# Sensor_node.net
KiCad netlist of a schematic drawn in Altium Designer
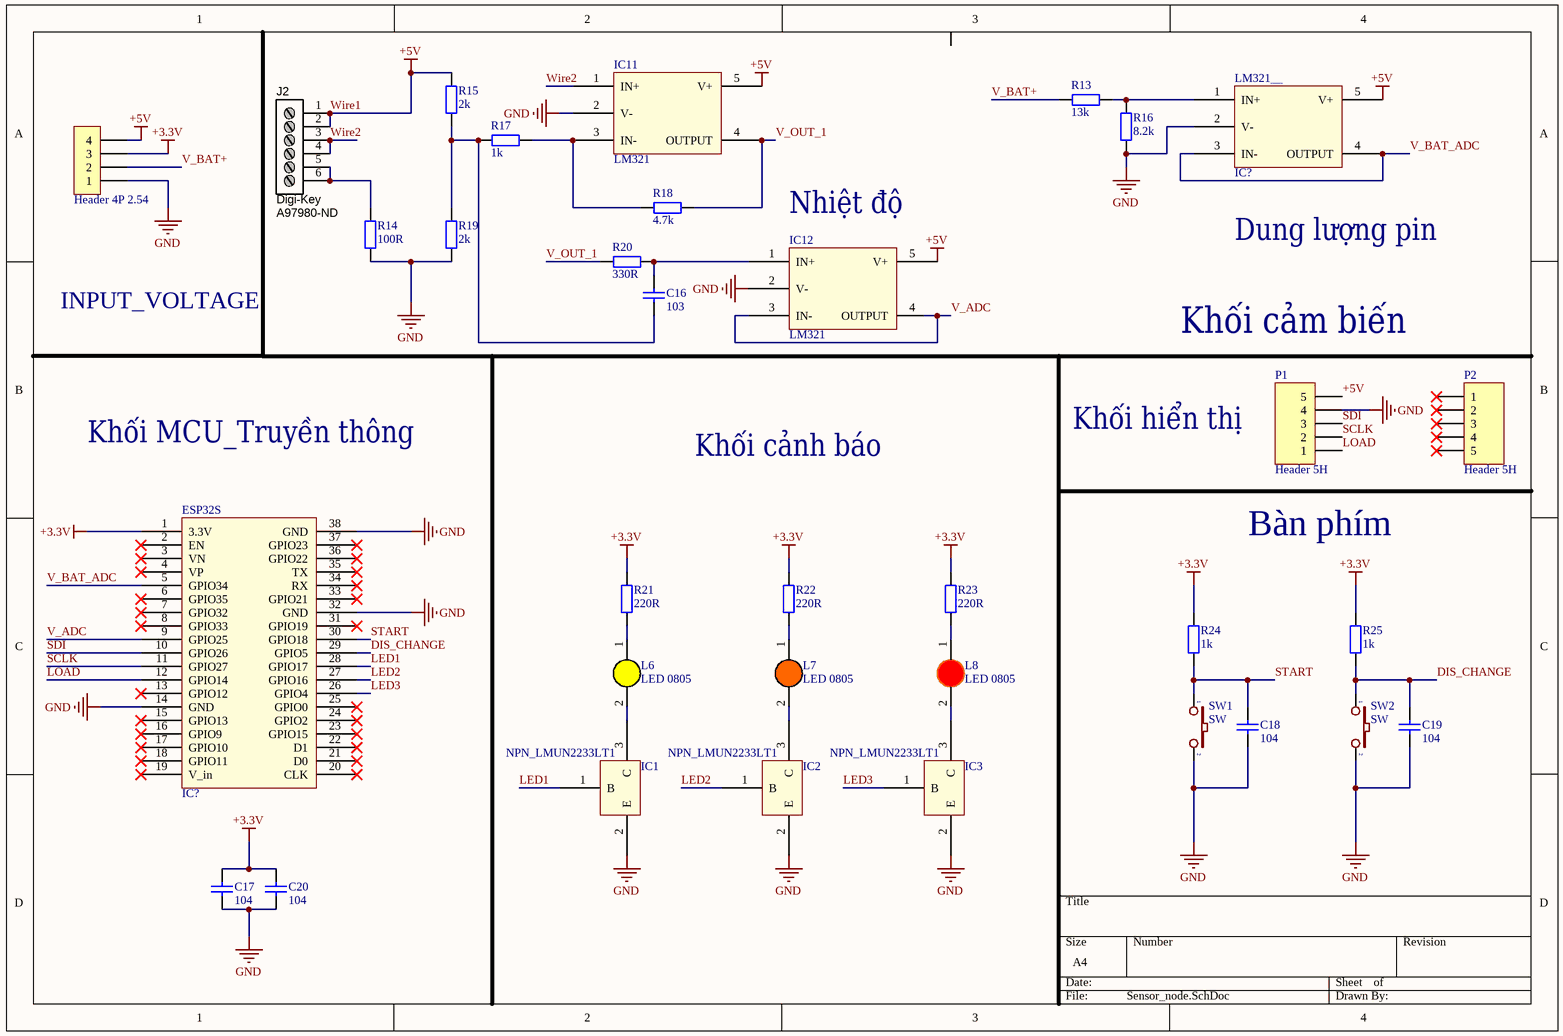
[diagram p0: Sensor_node.SchDoc]

(export (version "E")
  (design (tool "Eeschema 10.0.6"))
  (components
    (comp (ref "C16")
      (value "103")
      (footprint "tu gom")
      (description "Cắm")
      (libsource (lib "Altium_Lib_by_KhueNguyenCreator") (part "Tu gom 103 50V"))
    )
    (comp (ref "C17")
      (value "104")
      (footprint "tu 1206")
      (description "Dán")
      (libsource (lib "Altium_Lib_by_KhueNguyenCreator") (part "Tu 1206 104 50V 20%"))
    )
    (comp (ref "C18")
      (value "104")
      (footprint "tu gom")
      (description "Cắm")
      (libsource (lib "Altium_Lib_by_KhueNguyenCreator") (part "Tu gom 104 50V"))
    )
    (comp (ref "C19")
      (value "104")
      (footprint "tu gom")
      (description "Cắm")
      (libsource (lib "Altium_Lib_by_KhueNguyenCreator") (part "Tu gom 104 50V"))
    )
    (comp (ref "C20")
      (value "104")
      (footprint "tu 1206")
      (description "Dán")
      (libsource (lib "Altium_Lib_by_KhueNguyenCreator") (part "Tu 1206 104 50V 20%"))
    )
    (comp (ref "ESP32S") (value "IC?") (footprint "ESP32 DEVKIT") (libsource (lib "Schlib3") (part "IC?")))
    (comp (ref "H2")
      (value "Header 4P 2.54")
      (footprint "XH2.54M-4")
      (description "Cắm")
      (libsource (lib "Altium_Lib_by_KhueNguyenCreator") (part "Header 4P 2.54 Duc Thang"))
    )
    (comp (ref "IC1")
      (value "NPN_LMUN2233LT1")
      (footprint "SOT23_LMUN2233_trans")
      (libsource (lib "Schlib4") (part "NPN_LMUN2233LT1"))
    )
    (comp (ref "IC2")
      (value "NPN_LMUN2233LT1")
      (footprint "SOT23_LMUN2233_trans")
      (libsource (lib "Schlib4") (part "NPN_LMUN2233LT1"))
    )
    (comp (ref "IC3")
      (value "NPN_LMUN2233LT1")
      (footprint "SOT23_LMUN2233_trans")
      (libsource (lib "Schlib4") (part "NPN_LMUN2233LT1"))
    )
    (comp (ref "IC11") (value "LM321") (footprint "SOT23_LM321") (libsource (lib "Schlib2") (part "LM321")))
    (comp (ref "IC12") (value "LM321") (footprint "SOT23_LM321") (libsource (lib "Schlib2") (part "LM321")))
    (comp (ref "J2")
      (value "Stackable ScrewTerm")
      (footprint "6P_PCB_ScrewTerm_90S_3.81MM")
      (description "Terminal Block, THT, 6-Position screwterm, 3.81mm pitch")
      (fields (field (name "SUPPLIER 1") "Digi-Key") (field (name "SUPPLIER PART NUMBER 1") "A97980-ND"))
      (libsource (lib "My library altium") (part "6P_ScrewTerm_90S_3.81MM"))
    )
    (comp (ref "L6")
      (value "LED 0805")
      (footprint "LED-0805-Yellow")
      (description "Dán")
      (libsource (lib "Altium_Lib_by_KhueNguyenCreator") (part "LED 0805 Vang"))
    )
    (comp (ref "L7")
      (value "LED 0805")
      (footprint "LED-0805-Orange")
      (description "Dán")
      (libsource (lib "Altium_Lib_by_KhueNguyenCreator") (part "LED 0805 Cam"))
    )
    (comp (ref "L8")
      (value "LED 0805")
      (footprint "LED-0805-Red")
      (description "Dán")
      (libsource (lib "Altium_Lib_by_KhueNguyenCreator") (part "LED 0805 Do"))
    )
    (comp (ref "LM321__") (value "IC?") (footprint "SOT23_LM321") (libsource (lib "Schlib2") (part "IC?")))
    (comp (ref "P1")
      (value "Header 5H")
      (footprint "HDR1X5H")
      (description "Header, 5-Pin, Right Angle")
      (fields (field (name "PUBLISHER") "Altium Limited"))
      (libsource (lib "") (part "Header 5H_1"))
    )
    (comp (ref "P2")
      (value "Header 5H")
      (footprint "HDR1X5H")
      (description "Header, 5-Pin, Right Angle")
      (fields (field (name "PUBLISHER") "Altium Limited"))
      (libsource (lib "My library altium") (part "Header 5H"))
    )
    (comp (ref "R13")
      (value "13k")
      (footprint "tro smd 0805")
      (description "Dán")
      (libsource (lib "Altium_Lib_by_KhueNguyenCreator") (part "Tro 0805 5% 12k"))
    )
    (comp (ref "R14")
      (value "100R")
      (footprint "tro smd 1206")
      (description "Dán")
      (libsource (lib "Altium_Lib_by_KhueNguyenCreator") (part "Tro 1206 5% 100R"))
    )
    (comp (ref "R15")
      (value "2k")
      (footprint "tro smd 1206")
      (description "Dán")
      (libsource (lib "Altium_Lib_by_KhueNguyenCreator") (part "Tro 1206 5% 2k"))
    )
    (comp (ref "R16")
      (value "8.2k")
      (footprint "tro smd 0805")
      (description "Dán")
      (libsource (lib "Altium_Lib_by_KhueNguyenCreator") (part "Tro 0805 5% 8.2k"))
    )
    (comp (ref "R17")
      (value "1k")
      (footprint "tro smd 0805")
      (description "Dán")
      (libsource (lib "Altium_Lib_by_KhueNguyenCreator") (part "Tro 0805 5% 1k"))
    )
    (comp (ref "R18")
      (value "4.7k")
      (footprint "tro smd 0805")
      (description "Dán")
      (libsource (lib "Altium_Lib_by_KhueNguyenCreator") (part "Tro 0805 5% 4.7k"))
    )
    (comp (ref "R19")
      (value "2k")
      (footprint "tro smd 1206")
      (description "Dán")
      (libsource (lib "Altium_Lib_by_KhueNguyenCreator") (part "Tro 1206 5% 2k"))
    )
    (comp (ref "R20")
      (value "330R")
      (footprint "Tro SMD 0805")
      (description "Dán")
      (libsource (lib "Altium_Lib_by_KhueNguyenCreator") (part "Tro 0805 5% 330R"))
    )
    (comp (ref "R21")
      (value "220R")
      (footprint "tro smd 0805")
      (description "Dán")
      (libsource (lib "Altium_Lib_by_KhueNguyenCreator") (part "Tro 0805 5% 220R"))
    )
    (comp (ref "R22")
      (value "220R")
      (footprint "tro smd 0805")
      (description "Dán")
      (libsource (lib "Altium_Lib_by_KhueNguyenCreator") (part "Tro 0805 5% 220R"))
    )
    (comp (ref "R23")
      (value "220R")
      (footprint "tro smd 0805")
      (description "Dán")
      (libsource (lib "Altium_Lib_by_KhueNguyenCreator") (part "Tro 0805 5% 220R"))
    )
    (comp (ref "R24")
      (value "1k")
      (footprint "tro smd 0805")
      (description "Dán")
      (libsource (lib "Altium_Lib_by_KhueNguyenCreator") (part "Tro 0805 5% 1k"))
    )
    (comp (ref "R25")
      (value "1k")
      (footprint "tro smd 0805")
      (description "Dán")
      (libsource (lib "Altium_Lib_by_KhueNguyenCreator") (part "Tro 0805 5% 1k"))
    )
    (comp (ref "SW1")
      (value "SW")
      (footprint "SW2")
      (description "Switch button 2 pin")
      (libsource (lib "syhaunguyen") (part "SW2"))
    )
    (comp (ref "SW2")
      (value "SW")
      (footprint "SW2")
      (description "Switch button 2 pin")
      (libsource (lib "syhaunguyen") (part "SW2"))
    )
  )
  (nets
    (net (code "1") (name "+3.3V") (class "Default")
      (node (ref "C17") (pin "1") (pinfunction "1_1") (pintype "passive"))
      (node (ref "C20") (pin "1") (pinfunction "1_1") (pintype "passive"))
      (node (ref "ESP32S") (pin "1") (pinfunction "3.3V_1") (pintype "passive"))
      (node (ref "H2") (pin "3") (pinfunction "3_3") (pintype "passive"))
      (node (ref "R21") (pin "2") (pinfunction "2_2") (pintype "passive"))
      (node (ref "R22") (pin "2") (pinfunction "2_2") (pintype "passive"))
      (node (ref "R23") (pin "2") (pinfunction "2_2") (pintype "passive"))
      (node (ref "R24") (pin "2") (pinfunction "2_2") (pintype "passive"))
      (node (ref "R25") (pin "2") (pinfunction "2_2") (pintype "passive"))
    )
    (net (code "2") (name "+5V") (class "Default")
      (node (ref "H2") (pin "4") (pinfunction "4_4") (pintype "passive"))
      (node (ref "IC11") (pin "5") (pinfunction "V+_5") (pintype "passive"))
      (node (ref "IC12") (pin "5") (pinfunction "V+_5") (pintype "passive"))
      (node (ref "J2") (pin "1") (pinfunction "1_1") (pintype "passive"))
      (node (ref "J2") (pin "2") (pinfunction "2_2") (pintype "passive"))
      (node (ref "LM321__") (pin "5") (pinfunction "V+_5") (pintype "passive"))
      (node (ref "P1") (pin "5") (pinfunction "5_5") (pintype "passive"))
      (node (ref "R15") (pin "2") (pinfunction "2_2") (pintype "passive"))
    )
    (net (code "3") (name "/DIS_CHANGE") (class "Default")
      (node (ref "C19") (pin "1") (pinfunction "1_1") (pintype "passive"))
      (node (ref "ESP32S") (pin "29") (pinfunction "GPIO5_29") (pintype "passive"))
      (node (ref "R25") (pin "1") (pinfunction "1_1") (pintype "passive"))
      (node (ref "SW2") (pin "1") (pinfunction "1_1") (pintype "passive"))
    )
    (net (code "4") (name "/LED1") (class "Default")
      (node (ref "ESP32S") (pin "28") (pinfunction "GPIO17_28") (pintype "passive"))
      (node (ref "IC1") (pin "1") (pinfunction "B_1") (pintype "passive"))
    )
    (net (code "5") (name "/LED2") (class "Default")
      (node (ref "ESP32S") (pin "27") (pinfunction "GPIO16_27") (pintype "passive"))
      (node (ref "IC2") (pin "1") (pinfunction "B_1") (pintype "passive"))
    )
    (net (code "6") (name "/LED3") (class "Default")
      (node (ref "ESP32S") (pin "26") (pinfunction "GPIO4_26") (pintype "passive"))
      (node (ref "IC3") (pin "1") (pinfunction "B_1") (pintype "passive"))
    )
    (net (code "7") (name "/LOAD") (class "Default")
      (node (ref "ESP32S") (pin "12") (pinfunction "GPIO14_12") (pintype "passive"))
      (node (ref "P1") (pin "1") (pinfunction "1_1") (pintype "passive"))
    )
    (net (code "8") (name "/SCLK") (class "Default")
      (node (ref "ESP32S") (pin "11") (pinfunction "GPIO27_11") (pintype "passive"))
      (node (ref "P1") (pin "2") (pinfunction "2_2") (pintype "passive"))
    )
    (net (code "9") (name "/SDI") (class "Default")
      (node (ref "ESP32S") (pin "10") (pinfunction "GPIO26_10") (pintype "passive"))
      (node (ref "P1") (pin "3") (pinfunction "3_3") (pintype "passive"))
    )
    (net (code "10") (name "/START") (class "Default")
      (node (ref "C18") (pin "1") (pinfunction "1_1") (pintype "passive"))
      (node (ref "ESP32S") (pin "30") (pinfunction "GPIO18_30") (pintype "passive"))
      (node (ref "R24") (pin "1") (pinfunction "1_1") (pintype "passive"))
      (node (ref "SW1") (pin "1") (pinfunction "1_1") (pintype "passive"))
    )
    (net (code "11") (name "/V_ADC") (class "Default")
      (node (ref "ESP32S") (pin "9") (pinfunction "GPIO25_9") (pintype "passive"))
      (node (ref "IC12") (pin "3") (pinfunction "IN-_3") (pintype "passive"))
      (node (ref "IC12") (pin "4") (pinfunction "OUTPUT_4") (pintype "passive"))
    )
    (net (code "12") (name "/V_BAT+") (class "Default")
      (node (ref "H2") (pin "2") (pinfunction "2_2") (pintype "passive"))
      (node (ref "R13") (pin "1") (pinfunction "1_1") (pintype "passive"))
    )
    (net (code "13") (name "/V_BAT_ADC") (class "Default")
      (node (ref "ESP32S") (pin "5") (pinfunction "GPIO34_5") (pintype "passive"))
      (node (ref "LM321__") (pin "3") (pinfunction "IN-_3") (pintype "passive"))
      (node (ref "LM321__") (pin "4") (pinfunction "OUTPUT_4") (pintype "passive"))
    )
    (net (code "14") (name "/V_OUT_1") (class "Default")
      (node (ref "IC11") (pin "4") (pinfunction "OUTPUT_4") (pintype "passive"))
      (node (ref "R18") (pin "2") (pinfunction "2_2") (pintype "passive"))
      (node (ref "R20") (pin "1") (pinfunction "1_1") (pintype "passive"))
    )
    (net (code "15") (name "/Wire2") (class "Default")
      (node (ref "IC11") (pin "1") (pinfunction "IN+_1") (pintype "passive"))
      (node (ref "J2") (pin "3") (pinfunction "3_3") (pintype "passive"))
      (node (ref "J2") (pin "4") (pinfunction "4_4") (pintype "passive"))
    )
    (net (code "16") (name "GND") (class "Default")
      (node (ref "C17") (pin "2") (pinfunction "2_2") (pintype "passive"))
      (node (ref "C18") (pin "2") (pinfunction "2_2") (pintype "passive"))
      (node (ref "C19") (pin "2") (pinfunction "2_2") (pintype "passive"))
      (node (ref "C20") (pin "2") (pinfunction "2_2") (pintype "passive"))
      (node (ref "ESP32S") (pin "14") (pinfunction "GND_14") (pintype "passive"))
      (node (ref "ESP32S") (pin "32") (pinfunction "GND_32") (pintype "passive"))
      (node (ref "ESP32S") (pin "38") (pinfunction "GND_38") (pintype "passive"))
      (node (ref "H2") (pin "1") (pinfunction "1_1") (pintype "passive"))
      (node (ref "IC1") (pin "2") (pinfunction "E_2") (pintype "passive"))
      (node (ref "IC11") (pin "2") (pinfunction "V-_2") (pintype "passive"))
      (node (ref "IC12") (pin "2") (pinfunction "V-_2") (pintype "passive"))
      (node (ref "IC2") (pin "2") (pinfunction "E_2") (pintype "passive"))
      (node (ref "IC3") (pin "2") (pinfunction "E_2") (pintype "passive"))
      (node (ref "LM321__") (pin "2") (pinfunction "V-_2") (pintype "passive"))
      (node (ref "P1") (pin "4") (pinfunction "4_4") (pintype "passive"))
      (node (ref "R14") (pin "1") (pinfunction "1_1") (pintype "passive"))
      (node (ref "R16") (pin "1") (pinfunction "1_1") (pintype "passive"))
      (node (ref "R19") (pin "1") (pinfunction "1_1") (pintype "passive"))
      (node (ref "SW1") (pin "2") (pinfunction "2_2") (pintype "passive"))
      (node (ref "SW2") (pin "2") (pinfunction "2_2") (pintype "passive"))
    )
    (net (code "17") (name "Net-(C16-Pad2)") (class "Default")
      (node (ref "C16") (pin "2") (pinfunction "2_2") (pintype "passive"))
      (node (ref "R15") (pin "1") (pinfunction "1_1") (pintype "passive"))
      (node (ref "R17") (pin "1") (pinfunction "1_1") (pintype "passive"))
      (node (ref "R19") (pin "2") (pinfunction "2_2") (pintype "passive"))
    )
    (net (code "18") (name "Net-(IC1-C)") (class "Default")
      (node (ref "IC1") (pin "3") (pinfunction "C_3") (pintype "passive"))
      (node (ref "L6") (pin "2") (pinfunction "K_2") (pintype "passive"))
    )
    (net (code "19") (name "Net-(IC2-C)") (class "Default")
      (node (ref "IC2") (pin "3") (pinfunction "C_3") (pintype "passive"))
      (node (ref "L7") (pin "2") (pinfunction "K_2") (pintype "passive"))
    )
    (net (code "20") (name "Net-(IC3-C)") (class "Default")
      (node (ref "IC3") (pin "3") (pinfunction "C_3") (pintype "passive"))
      (node (ref "L8") (pin "2") (pinfunction "K_2") (pintype "passive"))
    )
    (net (code "21") (name "Net-(IC11-IN-)") (class "Default")
      (node (ref "IC11") (pin "3") (pinfunction "IN-_3") (pintype "passive"))
      (node (ref "R17") (pin "2") (pinfunction "2_2") (pintype "passive"))
      (node (ref "R18") (pin "1") (pinfunction "1_1") (pintype "passive"))
    )
    (net (code "22") (name "Net-(IC12-IN+)") (class "Default")
      (node (ref "C16") (pin "1") (pinfunction "1_1") (pintype "passive"))
      (node (ref "IC12") (pin "1") (pinfunction "IN+_1") (pintype "passive"))
      (node (ref "R20") (pin "2") (pinfunction "2_2") (pintype "passive"))
    )
    (net (code "23") (name "Net-(J2-Pad5)") (class "Default")
      (node (ref "J2") (pin "5") (pinfunction "5_5") (pintype "passive"))
      (node (ref "J2") (pin "6") (pinfunction "6_6") (pintype "passive"))
      (node (ref "R14") (pin "2") (pinfunction "2_2") (pintype "passive"))
    )
    (net (code "24") (name "Net-(L6-A)") (class "Default")
      (node (ref "L6") (pin "1") (pinfunction "A_1") (pintype "passive"))
      (node (ref "R21") (pin "1") (pinfunction "1_1") (pintype "passive"))
    )
    (net (code "25") (name "Net-(L7-A)") (class "Default")
      (node (ref "L7") (pin "1") (pinfunction "A_1") (pintype "passive"))
      (node (ref "R22") (pin "1") (pinfunction "1_1") (pintype "passive"))
    )
    (net (code "26") (name "Net-(L8-A)") (class "Default")
      (node (ref "L8") (pin "1") (pinfunction "A_1") (pintype "passive"))
      (node (ref "R23") (pin "1") (pinfunction "1_1") (pintype "passive"))
    )
    (net (code "27") (name "Net-(LM321__-IN+)") (class "Default")
      (node (ref "LM321__") (pin "1") (pinfunction "IN+_1") (pintype "passive"))
      (node (ref "R13") (pin "2") (pinfunction "2_2") (pintype "passive"))
      (node (ref "R16") (pin "2") (pinfunction "2_2") (pintype "passive"))
    )
    (net (code "28") (name "unconnected-(ESP32S-CLK-Pad20)") (class "Default")
      (node (ref "ESP32S") (pin "20") (pinfunction "CLK_20") (pintype "passive+no_connect"))
    )
    (net (code "29") (name "unconnected-(ESP32S-D0-Pad21)") (class "Default")
      (node (ref "ESP32S") (pin "21") (pinfunction "D0_21") (pintype "passive+no_connect"))
    )
    (net (code "30") (name "unconnected-(ESP32S-D1-Pad22)") (class "Default")
      (node (ref "ESP32S") (pin "22") (pinfunction "D1_22") (pintype "passive+no_connect"))
    )
    (net (code "31") (name "unconnected-(ESP32S-EN-Pad2)") (class "Default")
      (node (ref "ESP32S") (pin "2") (pinfunction "EN_2") (pintype "passive+no_connect"))
    )
    (net (code "32") (name "unconnected-(ESP32S-GPIO0-Pad25)") (class "Default")
      (node (ref "ESP32S") (pin "25") (pinfunction "GPIO0_25") (pintype "passive+no_connect"))
    )
    (net (code "33") (name "unconnected-(ESP32S-GPIO2-Pad24)") (class "Default")
      (node (ref "ESP32S") (pin "24") (pinfunction "GPIO2_24") (pintype "passive+no_connect"))
    )
    (net (code "34") (name "unconnected-(ESP32S-GPIO9-Pad16)") (class "Default")
      (node (ref "ESP32S") (pin "16") (pinfunction "GPIO9_16") (pintype "passive+no_connect"))
    )
    (net (code "35") (name "unconnected-(ESP32S-GPIO10-Pad17)") (class "Default")
      (node (ref "ESP32S") (pin "17") (pinfunction "GPIO10_17") (pintype "passive+no_connect"))
    )
    (net (code "36") (name "unconnected-(ESP32S-GPIO11-Pad18)") (class "Default")
      (node (ref "ESP32S") (pin "18") (pinfunction "GPIO11_18") (pintype "passive+no_connect"))
    )
    (net (code "37") (name "unconnected-(ESP32S-GPIO12-Pad13)") (class "Default")
      (node (ref "ESP32S") (pin "13") (pinfunction "GPIO12_13") (pintype "passive+no_connect"))
    )
    (net (code "38") (name "unconnected-(ESP32S-GPIO13-Pad15)") (class "Default")
      (node (ref "ESP32S") (pin "15") (pinfunction "GPIO13_15") (pintype "passive+no_connect"))
    )
    (net (code "39") (name "unconnected-(ESP32S-GPIO15-Pad23)") (class "Default")
      (node (ref "ESP32S") (pin "23") (pinfunction "GPIO15_23") (pintype "passive+no_connect"))
    )
    (net (code "40") (name "unconnected-(ESP32S-GPIO19-Pad31)") (class "Default")
      (node (ref "ESP32S") (pin "31") (pinfunction "GPIO19_31") (pintype "passive+no_connect"))
    )
    (net (code "41") (name "unconnected-(ESP32S-GPIO21-Pad33)") (class "Default")
      (node (ref "ESP32S") (pin "33") (pinfunction "GPIO21_33") (pintype "passive+no_connect"))
    )
    (net (code "42") (name "unconnected-(ESP32S-GPIO22-Pad36)") (class "Default")
      (node (ref "ESP32S") (pin "36") (pinfunction "GPIO22_36") (pintype "passive+no_connect"))
    )
    (net (code "43") (name "unconnected-(ESP32S-GPIO23-Pad37)") (class "Default")
      (node (ref "ESP32S") (pin "37") (pinfunction "GPIO23_37") (pintype "passive+no_connect"))
    )
    (net (code "44") (name "unconnected-(ESP32S-GPIO32-Pad7)") (class "Default")
      (node (ref "ESP32S") (pin "7") (pinfunction "GPIO32_7") (pintype "passive+no_connect"))
    )
    (net (code "45") (name "unconnected-(ESP32S-GPIO33-Pad8)") (class "Default")
      (node (ref "ESP32S") (pin "8") (pinfunction "GPIO33_8") (pintype "passive+no_connect"))
    )
    (net (code "46") (name "unconnected-(ESP32S-GPIO35-Pad6)") (class "Default")
      (node (ref "ESP32S") (pin "6") (pinfunction "GPIO35_6") (pintype "passive+no_connect"))
    )
    (net (code "47") (name "unconnected-(ESP32S-RX-Pad34)") (class "Default")
      (node (ref "ESP32S") (pin "34") (pinfunction "RX_34") (pintype "passive+no_connect"))
    )
    (net (code "48") (name "unconnected-(ESP32S-TX-Pad35)") (class "Default")
      (node (ref "ESP32S") (pin "35") (pinfunction "TX_35") (pintype "passive+no_connect"))
    )
    (net (code "49") (name "unconnected-(ESP32S-VN-Pad3)") (class "Default")
      (node (ref "ESP32S") (pin "3") (pinfunction "VN_3") (pintype "passive+no_connect"))
    )
    (net (code "50") (name "unconnected-(ESP32S-VP-Pad4)") (class "Default")
      (node (ref "ESP32S") (pin "4") (pinfunction "VP_4") (pintype "passive+no_connect"))
    )
    (net (code "51") (name "unconnected-(ESP32S-V_in-Pad19)") (class "Default")
      (node (ref "ESP32S") (pin "19") (pinfunction "V_in_19") (pintype "passive+no_connect"))
    )
    (net (code "52") (name "unconnected-(P2-Pad1)") (class "Default")
      (node (ref "P2") (pin "1") (pinfunction "1_1") (pintype "passive+no_connect"))
    )
    (net (code "53") (name "unconnected-(P2-Pad2)") (class "Default")
      (node (ref "P2") (pin "2") (pinfunction "2_2") (pintype "passive+no_connect"))
    )
    (net (code "54") (name "unconnected-(P2-Pad3)") (class "Default")
      (node (ref "P2") (pin "3") (pinfunction "3_3") (pintype "passive+no_connect"))
    )
    (net (code "55") (name "unconnected-(P2-Pad4)") (class "Default")
      (node (ref "P2") (pin "4") (pinfunction "4_4") (pintype "passive+no_connect"))
    )
    (net (code "56") (name "unconnected-(P2-Pad5)") (class "Default")
      (node (ref "P2") (pin "5") (pinfunction "5_5") (pintype "passive+no_connect"))
    )
  )
)
